# MCU-Debug.net
KiCad netlist of a schematic drawn in Altium Designer
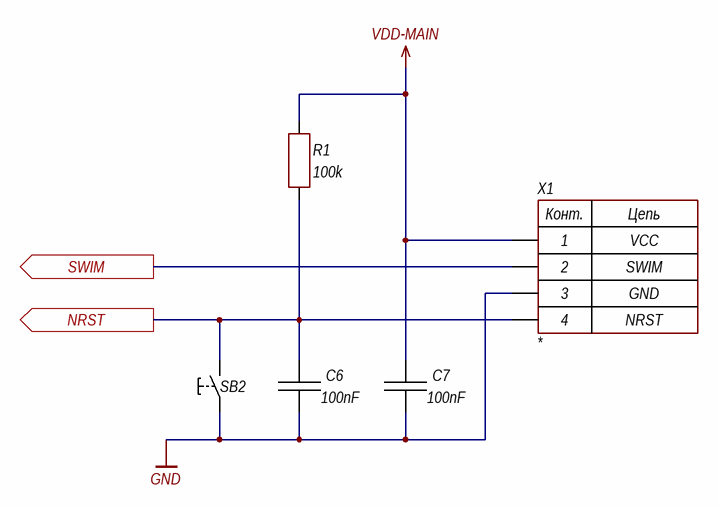
[diagram p0: MCU-Debug.SchDoc]

(export (version "E")
  (design (tool "Eeschema 10.0.6"))
  (components
    (comp (ref "C6") (value "100nF") (footprint "CH0402C") (libsource (lib "Discrete") (part "Capacitor")))
    (comp (ref "C7") (value "100nF") (footprint "CH0402C") (libsource (lib "Discrete") (part "Capacitor")))
    (comp (ref "R1") (value "100k") (footprint "CH0402R") (libsource (lib "Discrete") (part "Resistor")))
    (comp (ref "SB2")
      (value "\"Кнопка\"")
      (footprint "BUT: YTS-A017")
      (description "Button, no latching")
      (libsource (lib "Connectors") (part "1-Button"))
    )
    (comp (ref "X1") (value "*") (footprint "CON: PLS-4") (libsource (lib "Connectors") (part "4-Connector")))
  )
  (nets
    (net (code "1") (name "/NRST") (class "Default")
      (node (ref "C6") (pin "2") (pinfunction "2_2") (pintype "passive"))
      (node (ref "R1") (pin "1") (pinfunction "1_1") (pintype "passive"))
      (node (ref "SB2") (pin "2") (pinfunction "2_2") (pintype "passive"))
      (node (ref "X1") (pin "4") (pinfunction "4_4") (pintype "passive"))
    )
    (net (code "2") (name "/SWIM") (class "Default")
      (node (ref "X1") (pin "2") (pinfunction "2_2") (pintype "passive"))
    )
    (net (code "3") (name "GND") (class "Default")
      (node (ref "C6") (pin "1") (pinfunction "1_1") (pintype "passive"))
      (node (ref "C7") (pin "1") (pinfunction "1_1") (pintype "passive"))
      (node (ref "SB2") (pin "1") (pinfunction "1_1") (pintype "passive"))
      (node (ref "X1") (pin "3") (pinfunction "3_3") (pintype "passive"))
    )
    (net (code "4") (name "VDD-MAIN") (class "Default")
      (node (ref "C7") (pin "2") (pinfunction "2_2") (pintype "passive"))
      (node (ref "R1") (pin "2") (pinfunction "2_2") (pintype "passive"))
      (node (ref "X1") (pin "1") (pinfunction "1_1") (pintype "passive"))
    )
  )
)
